# abs_555.net
KiCad netlist of a schematic drawn in EAGLE
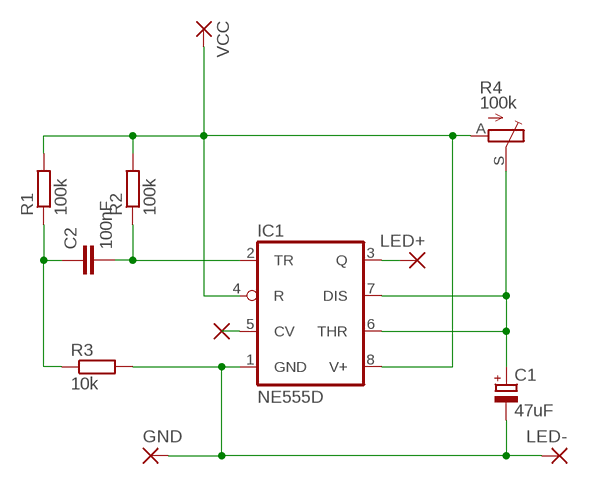
[diagram p0: schematic, sheet 1]

(export (version "E")
  (design (tool "Eeschema 10.0.6"))
  (components
    (comp (ref "C1")
      (value "47uF")
      (footprint "eagle-import:D_7343-31W")
      (libsource (lib "eagle-import") (part "CPOL-EUD/7343-31W"))
    )
    (comp (ref "C2")
      (value "100nF")
      (footprint "eagle-import:C0805")
      (libsource (lib "eagle-import") (part "C-EUC0805"))
    )
    (comp (ref "GND")
      (value "2,54/0,8")
      (footprint "eagle-import:2,54_0,8")
      (libsource (lib "eagle-import") (part "2,54/0,8"))
    )
    (comp (ref "IC1")
      (value "NE555D")
      (footprint "eagle-import:SO08")
      (libsource (lib "eagle-import") (part "555DNE"))
    )
    (comp (ref "LED+")
      (value "2,54/0,8")
      (footprint "eagle-import:2,54_0,8")
      (libsource (lib "eagle-import") (part "2,54/0,8"))
    )
    (comp (ref "LED-")
      (value "2,54/0,8")
      (footprint "eagle-import:2,54_0,8")
      (libsource (lib "eagle-import") (part "2,54/0,8"))
    )
    (comp (ref "NC")
      (value "0.1MMPAD")
      (footprint "eagle-import:PADS")
      (libsource (lib "eagle-import") (part "0.1MMPAD"))
    )
    (comp (ref "R1")
      (value "100k")
      (footprint "eagle-import:R0805")
      (libsource (lib "eagle-import") (part "R-EU_R0805"))
    )
    (comp (ref "R2")
      (value "100k")
      (footprint "eagle-import:R0805")
      (libsource (lib "eagle-import") (part "R-EU_R0805"))
    )
    (comp (ref "R3")
      (value "10k")
      (footprint "eagle-import:R0805")
      (libsource (lib "eagle-import") (part "R-EU_R0805"))
    )
    (comp (ref "R4")
      (value "100k")
      (footprint "eagle-import:CA6V")
      (libsource (lib "eagle-import") (part "TRIM_EU-CA6V"))
    )
    (comp (ref "VCC")
      (value "2,54/0,8")
      (footprint "eagle-import:2,54_0,8")
      (libsource (lib "eagle-import") (part "2,54/0,8"))
    )
  )
  (nets
    (net (code "1") (name "Net-(C2-Pad1)") (class "Default")
      (node (ref "C2") (pin "1") (pinfunction "1_1") (pintype "passive"))
      (node (ref "R1") (pin "1") (pinfunction "1_1") (pintype "passive"))
      (node (ref "R3") (pin "1") (pinfunction "1_1") (pintype "passive"))
    )
    (net (code "2") (name "Net-(GND-P)") (class "Default")
      (node (ref "C1") (pin "-") (pinfunction "-_-") (pintype "passive"))
      (node (ref "GND") (pin "1") (pinfunction "P_1") (pintype "passive"))
      (node (ref "IC1") (pin "1") (pinfunction "GND_1") (pintype "power_in"))
      (node (ref "LED-") (pin "1") (pinfunction "P_1") (pintype "passive"))
      (node (ref "R3") (pin "2") (pinfunction "2_2") (pintype "passive"))
    )
    (net (code "3") (name "Net-(IC1-CV)") (class "Default")
      (node (ref "IC1") (pin "5") (pinfunction "CV_5") (pintype "input"))
      (node (ref "NC") (pin "1") (pinfunction "P_1") (pintype "passive"))
    )
    (net (code "4") (name "Net-(IC1-DIS)") (class "Default")
      (node (ref "C1") (pin "+") (pinfunction "+_+") (pintype "passive"))
      (node (ref "IC1") (pin "6") (pinfunction "THR_6") (pintype "input"))
      (node (ref "IC1") (pin "7") (pinfunction "DIS_7") (pintype "input"))
      (node (ref "R4") (pin "S") (pinfunction "S_S") (pintype "passive"))
    )
    (net (code "5") (name "Net-(IC1-Q)") (class "Default")
      (node (ref "IC1") (pin "3") (pinfunction "Q_3") (pintype "output"))
      (node (ref "LED+") (pin "1") (pinfunction "P_1") (pintype "passive"))
    )
    (net (code "6") (name "Net-(IC1-R)") (class "Default")
      (node (ref "IC1") (pin "4") (pinfunction "R_4") (pintype "input"))
      (node (ref "IC1") (pin "8") (pinfunction "V+_8") (pintype "power_in"))
      (node (ref "R1") (pin "2") (pinfunction "2_2") (pintype "passive"))
      (node (ref "R2") (pin "2") (pinfunction "2_2") (pintype "passive"))
      (node (ref "R4") (pin "A") (pinfunction "A_A") (pintype "passive"))
      (node (ref "VCC") (pin "1") (pinfunction "P_1") (pintype "passive"))
    )
    (net (code "7") (name "Net-(IC1-TR)") (class "Default")
      (node (ref "C2") (pin "2") (pinfunction "2_2") (pintype "passive"))
      (node (ref "IC1") (pin "2") (pinfunction "TR_2") (pintype "input"))
      (node (ref "R2") (pin "1") (pinfunction "1_1") (pintype "passive"))
    )
  )
)
